# Touch_V5.net
KiCad netlist of a schematic drawn in EAGLE
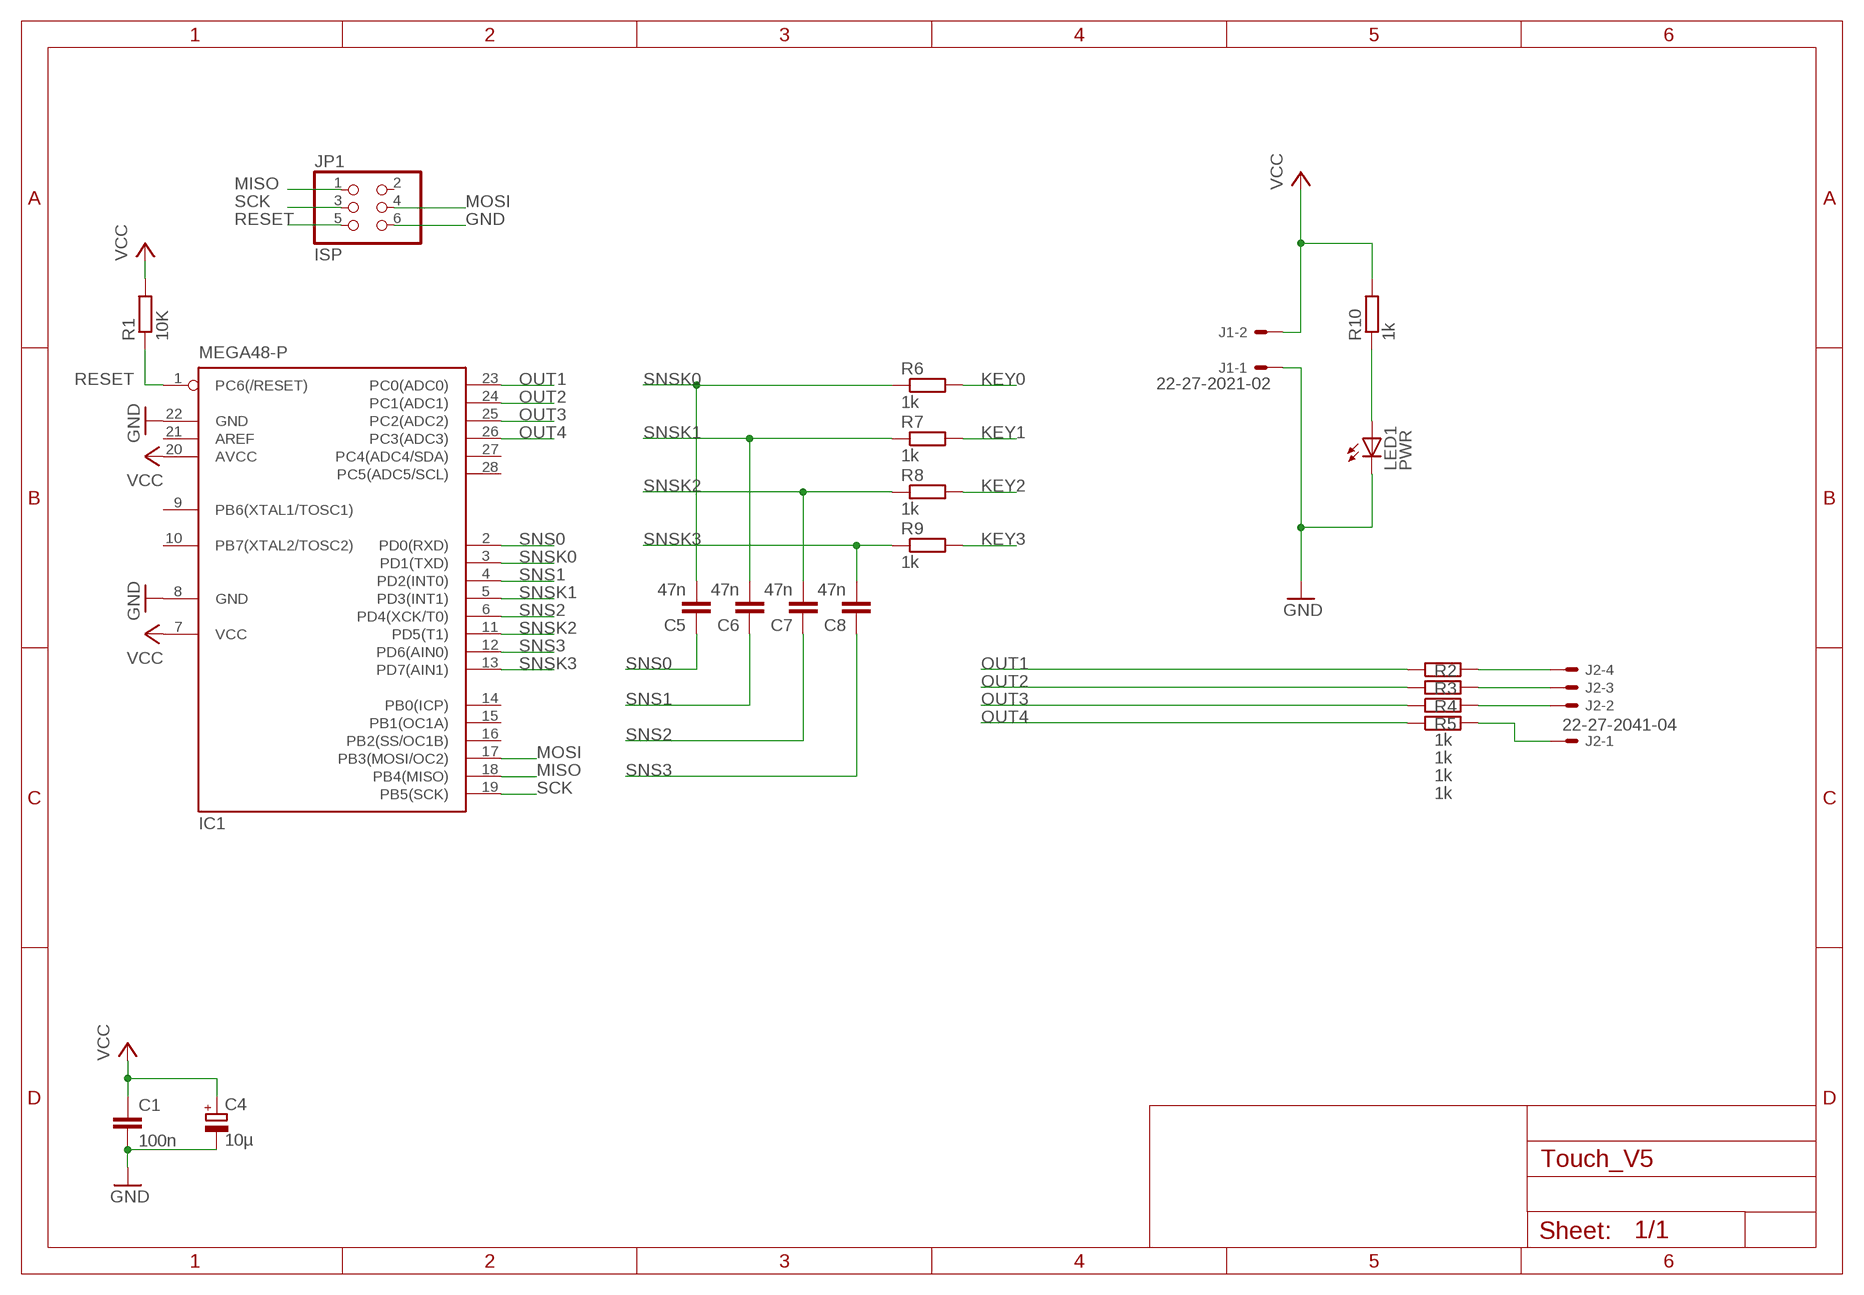
[diagram p0: schematic, sheet 1]

(export (version "E")
  (design (tool "Eeschema 10.0.6"))
  (components
    (comp (ref "C1")
      (value "100n")
      (footprint "eagle-import:C050-025X075")
      (libsource (lib "eagle-import") (part "C-EU050-025X075"))
    )
    (comp (ref "C4")
      (value "10µ")
      (footprint "eagle-import:E2-5")
      (libsource (lib "eagle-import") (part "CPOL-EUE2-5"))
    )
    (comp (ref "C5")
      (value "47n")
      (footprint "eagle-import:C050-025X075")
      (libsource (lib "eagle-import") (part "C-EU050-025X075"))
    )
    (comp (ref "C6")
      (value "47n")
      (footprint "eagle-import:C050-025X075")
      (libsource (lib "eagle-import") (part "C-EU050-025X075"))
    )
    (comp (ref "C7")
      (value "47n")
      (footprint "eagle-import:C050-025X075")
      (libsource (lib "eagle-import") (part "C-EU050-025X075"))
    )
    (comp (ref "C8")
      (value "47n")
      (footprint "eagle-import:C050-025X075")
      (libsource (lib "eagle-import") (part "C-EU050-025X075"))
    )
    (comp (ref "IC1")
      (value "MEGA48-P")
      (footprint "eagle-import:DIL28-3")
      (libsource (lib "eagle-import") (part "MEGA8-P"))
    )
    (comp (ref "J1")
      (value "22-27-2021-02")
      (footprint "eagle-import:6410-02")
      (libsource (lib "eagle-import") (part "22-?-0227-2021"))
    )
    (comp (ref "J2")
      (value "22-27-2041-04")
      (footprint "eagle-import:6410-04")
      (libsource (lib "eagle-import") (part "22-?-0427-2041"))
    )
    (comp (ref "JP1")
      (value "ISP")
      (footprint "eagle-import:2X03")
      (libsource (lib "eagle-import") (part "PINHD-2X3"))
    )
    (comp (ref "LED1")
      (value "PWR")
      (footprint "eagle-import:LED3MM")
      (libsource (lib "eagle-import") (part "LED3MM"))
    )
    (comp (ref "R1")
      (value "10K")
      (footprint "eagle-import:0207_10")
      (libsource (lib "eagle-import") (part "R-EU_0207/10"))
    )
    (comp (ref "R2")
      (value "1k")
      (footprint "eagle-import:0207_10")
      (libsource (lib "eagle-import") (part "R-EU_0207/10"))
    )
    (comp (ref "R3")
      (value "1k")
      (footprint "eagle-import:0207_10")
      (libsource (lib "eagle-import") (part "R-EU_0207/10"))
    )
    (comp (ref "R4")
      (value "1k")
      (footprint "eagle-import:0207_10")
      (libsource (lib "eagle-import") (part "R-EU_0207/10"))
    )
    (comp (ref "R5")
      (value "1k")
      (footprint "eagle-import:0207_10")
      (libsource (lib "eagle-import") (part "R-EU_0207/10"))
    )
    (comp (ref "R6")
      (value "1k")
      (footprint "eagle-import:0207_10")
      (libsource (lib "eagle-import") (part "R-EU_0207/10"))
    )
    (comp (ref "R7")
      (value "1k")
      (footprint "eagle-import:0207_10")
      (libsource (lib "eagle-import") (part "R-EU_0207/10"))
    )
    (comp (ref "R8")
      (value "1k")
      (footprint "eagle-import:0207_10")
      (libsource (lib "eagle-import") (part "R-EU_0207/10"))
    )
    (comp (ref "R9")
      (value "1k")
      (footprint "eagle-import:0207_10")
      (libsource (lib "eagle-import") (part "R-EU_0207/10"))
    )
    (comp (ref "R10")
      (value "1k")
      (footprint "eagle-import:0207_10")
      (libsource (lib "eagle-import") (part "R-EU_0207/10"))
    )
  )
  (nets
    (net (code "1") (name "/KEY0") (class "Default")
      (node (ref "R6") (pin "2") (pinfunction "2_2") (pintype "passive"))
    )
    (net (code "2") (name "/KEY1") (class "Default")
      (node (ref "R7") (pin "2") (pinfunction "2_2") (pintype "passive"))
    )
    (net (code "3") (name "/KEY2") (class "Default")
      (node (ref "R8") (pin "2") (pinfunction "2_2") (pintype "passive"))
    )
    (net (code "4") (name "/KEY3") (class "Default")
      (node (ref "R9") (pin "2") (pinfunction "2_2") (pintype "passive"))
    )
    (net (code "5") (name "/MISO") (class "Default")
      (node (ref "IC1") (pin "18") (pinfunction "PB4(MISO)_18") (pintype "bidirectional"))
      (node (ref "JP1") (pin "1") (pinfunction "1_1") (pintype "passive"))
    )
    (net (code "6") (name "/MOSI") (class "Default")
      (node (ref "IC1") (pin "17") (pinfunction "PB3(MOSI/OC2)_17") (pintype "bidirectional"))
      (node (ref "JP1") (pin "4") (pinfunction "4_4") (pintype "passive"))
    )
    (net (code "7") (name "/OUT1") (class "Default")
      (node (ref "IC1") (pin "23") (pinfunction "PC0(ADC0)_23") (pintype "bidirectional"))
      (node (ref "R2") (pin "1") (pinfunction "1_1") (pintype "passive"))
    )
    (net (code "8") (name "/OUT2") (class "Default")
      (node (ref "IC1") (pin "24") (pinfunction "PC1(ADC1)_24") (pintype "bidirectional"))
      (node (ref "R3") (pin "1") (pinfunction "1_1") (pintype "passive"))
    )
    (net (code "9") (name "/OUT3") (class "Default")
      (node (ref "IC1") (pin "25") (pinfunction "PC2(ADC2)_25") (pintype "bidirectional"))
      (node (ref "R4") (pin "1") (pinfunction "1_1") (pintype "passive"))
    )
    (net (code "10") (name "/OUT4") (class "Default")
      (node (ref "IC1") (pin "26") (pinfunction "PC3(ADC3)_26") (pintype "bidirectional"))
      (node (ref "R5") (pin "1") (pinfunction "1_1") (pintype "passive"))
    )
    (net (code "11") (name "/RESET") (class "Default")
      (node (ref "IC1") (pin "1") (pinfunction "PC6(/RESET)_1") (pintype "bidirectional"))
      (node (ref "JP1") (pin "5") (pinfunction "5_5") (pintype "passive"))
      (node (ref "R1") (pin "1") (pinfunction "1_1") (pintype "passive"))
    )
    (net (code "12") (name "/SCK") (class "Default")
      (node (ref "IC1") (pin "19") (pinfunction "PB5(SCK)_19") (pintype "bidirectional"))
      (node (ref "JP1") (pin "3") (pinfunction "3_3") (pintype "passive"))
    )
    (net (code "13") (name "/SNS0") (class "Default")
      (node (ref "C5") (pin "1") (pinfunction "1_1") (pintype "passive"))
      (node (ref "IC1") (pin "2") (pinfunction "PD0(RXD)_2") (pintype "bidirectional"))
    )
    (net (code "14") (name "/SNS1") (class "Default")
      (node (ref "C6") (pin "1") (pinfunction "1_1") (pintype "passive"))
      (node (ref "IC1") (pin "4") (pinfunction "PD2(INT0)_4") (pintype "bidirectional"))
    )
    (net (code "15") (name "/SNS2") (class "Default")
      (node (ref "C7") (pin "1") (pinfunction "1_1") (pintype "passive"))
      (node (ref "IC1") (pin "6") (pinfunction "PD4(XCK/T0)_6") (pintype "bidirectional"))
    )
    (net (code "16") (name "/SNS3") (class "Default")
      (node (ref "C8") (pin "1") (pinfunction "1_1") (pintype "passive"))
      (node (ref "IC1") (pin "12") (pinfunction "PD6(AIN0)_12") (pintype "bidirectional"))
    )
    (net (code "17") (name "/SNSK0") (class "Default")
      (node (ref "C5") (pin "2") (pinfunction "2_2") (pintype "passive"))
      (node (ref "IC1") (pin "3") (pinfunction "PD1(TXD)_3") (pintype "bidirectional"))
      (node (ref "R6") (pin "1") (pinfunction "1_1") (pintype "passive"))
    )
    (net (code "18") (name "/SNSK1") (class "Default")
      (node (ref "C6") (pin "2") (pinfunction "2_2") (pintype "passive"))
      (node (ref "IC1") (pin "5") (pinfunction "PD3(INT1)_5") (pintype "bidirectional"))
      (node (ref "R7") (pin "1") (pinfunction "1_1") (pintype "passive"))
    )
    (net (code "19") (name "/SNSK2") (class "Default")
      (node (ref "C7") (pin "2") (pinfunction "2_2") (pintype "passive"))
      (node (ref "IC1") (pin "11") (pinfunction "PD5(T1)_11") (pintype "bidirectional"))
      (node (ref "R8") (pin "1") (pinfunction "1_1") (pintype "passive"))
    )
    (net (code "20") (name "/SNSK3") (class "Default")
      (node (ref "C8") (pin "2") (pinfunction "2_2") (pintype "passive"))
      (node (ref "IC1") (pin "13") (pinfunction "PD7(AIN1)_13") (pintype "bidirectional"))
      (node (ref "R9") (pin "1") (pinfunction "1_1") (pintype "passive"))
    )
    (net (code "21") (name "GND") (class "Default")
      (node (ref "C1") (pin "2") (pinfunction "2_2") (pintype "passive"))
      (node (ref "C4") (pin "-") (pinfunction "-_-") (pintype "passive"))
      (node (ref "IC1") (pin "22") (pinfunction "GND_22") (pintype "power_in"))
      (node (ref "IC1") (pin "8") (pinfunction "GND_8") (pintype "power_in"))
      (node (ref "J1") (pin "1") (pinfunction "S_1") (pintype "passive"))
      (node (ref "JP1") (pin "6") (pinfunction "6_6") (pintype "passive"))
      (node (ref "LED1") (pin "K") (pinfunction "C_K") (pintype "passive"))
    )
    (net (code "22") (name "Net-(J2A-S)") (class "Default")
      (node (ref "J2") (pin "1") (pinfunction "S_1") (pintype "passive"))
      (node (ref "R5") (pin "2") (pinfunction "2_2") (pintype "passive"))
    )
    (net (code "23") (name "Net-(J2B-S)") (class "Default")
      (node (ref "J2") (pin "2") (pinfunction "S_2") (pintype "passive"))
      (node (ref "R4") (pin "2") (pinfunction "2_2") (pintype "passive"))
    )
    (net (code "24") (name "Net-(J2C-S)") (class "Default")
      (node (ref "J2") (pin "3") (pinfunction "S_3") (pintype "passive"))
      (node (ref "R3") (pin "2") (pinfunction "2_2") (pintype "passive"))
    )
    (net (code "25") (name "Net-(J2D-S)") (class "Default")
      (node (ref "J2") (pin "4") (pinfunction "S_4") (pintype "passive"))
      (node (ref "R2") (pin "2") (pinfunction "2_2") (pintype "passive"))
    )
    (net (code "26") (name "Net-(LED1-PadA)") (class "Default")
      (node (ref "LED1") (pin "A") (pinfunction "A_A") (pintype "passive"))
      (node (ref "R10") (pin "1") (pinfunction "1_1") (pintype "passive"))
    )
    (net (code "27") (name "VCC") (class "Default")
      (node (ref "C1") (pin "1") (pinfunction "1_1") (pintype "passive"))
      (node (ref "C4") (pin "+") (pinfunction "+_+") (pintype "passive"))
      (node (ref "IC1") (pin "20") (pinfunction "AVCC_20") (pintype "power_in"))
      (node (ref "IC1") (pin "7") (pinfunction "VCC_7") (pintype "power_in"))
      (node (ref "J1") (pin "2") (pinfunction "S_2") (pintype "passive"))
      (node (ref "R1") (pin "2") (pinfunction "2_2") (pintype "passive"))
      (node (ref "R10") (pin "2") (pinfunction "2_2") (pintype "passive"))
    )
    (net (code "28") (name "unconnected-(IC1-AREF-Pad21)") (class "Default")
      (node (ref "IC1") (pin "21") (pinfunction "AREF_21") (pintype "passive"))
    )
    (net (code "29") (name "unconnected-(IC1-PB0(ICP)-Pad14)") (class "Default")
      (node (ref "IC1") (pin "14") (pinfunction "PB0(ICP)_14") (pintype "bidirectional"))
    )
    (net (code "30") (name "unconnected-(IC1-PB1(OC1A)-Pad15)") (class "Default")
      (node (ref "IC1") (pin "15") (pinfunction "PB1(OC1A)_15") (pintype "bidirectional"))
    )
    (net (code "31") (name "unconnected-(IC1-PB2(SS{slash}OC1B)-Pad16)") (class "Default")
      (node (ref "IC1") (pin "16") (pinfunction "PB2(SS/OC1B)_16") (pintype "bidirectional"))
    )
    (net (code "32") (name "unconnected-(IC1-PB6(XTAL1{slash}TOSC1)-Pad9)") (class "Default")
      (node (ref "IC1") (pin "9") (pinfunction "PB6(XTAL1/TOSC1)_9") (pintype "bidirectional"))
    )
    (net (code "33") (name "unconnected-(IC1-PB7(XTAL2{slash}TOSC2)-Pad10)") (class "Default")
      (node (ref "IC1") (pin "10") (pinfunction "PB7(XTAL2/TOSC2)_10") (pintype "bidirectional"))
    )
    (net (code "34") (name "unconnected-(IC1-PC4(ADC4{slash}SDA)-Pad27)") (class "Default")
      (node (ref "IC1") (pin "27") (pinfunction "PC4(ADC4/SDA)_27") (pintype "bidirectional"))
    )
    (net (code "35") (name "unconnected-(IC1-PC5(ADC5{slash}SCL)-Pad28)") (class "Default")
      (node (ref "IC1") (pin "28") (pinfunction "PC5(ADC5/SCL)_28") (pintype "bidirectional"))
    )
    (net (code "36") (name "unconnected-(JP1-Pad2)") (class "Default")
      (node (ref "JP1") (pin "2") (pinfunction "2_2") (pintype "passive"))
    )
  )
)
